# photodiode.net
KiCad netlist of a schematic drawn in EAGLE
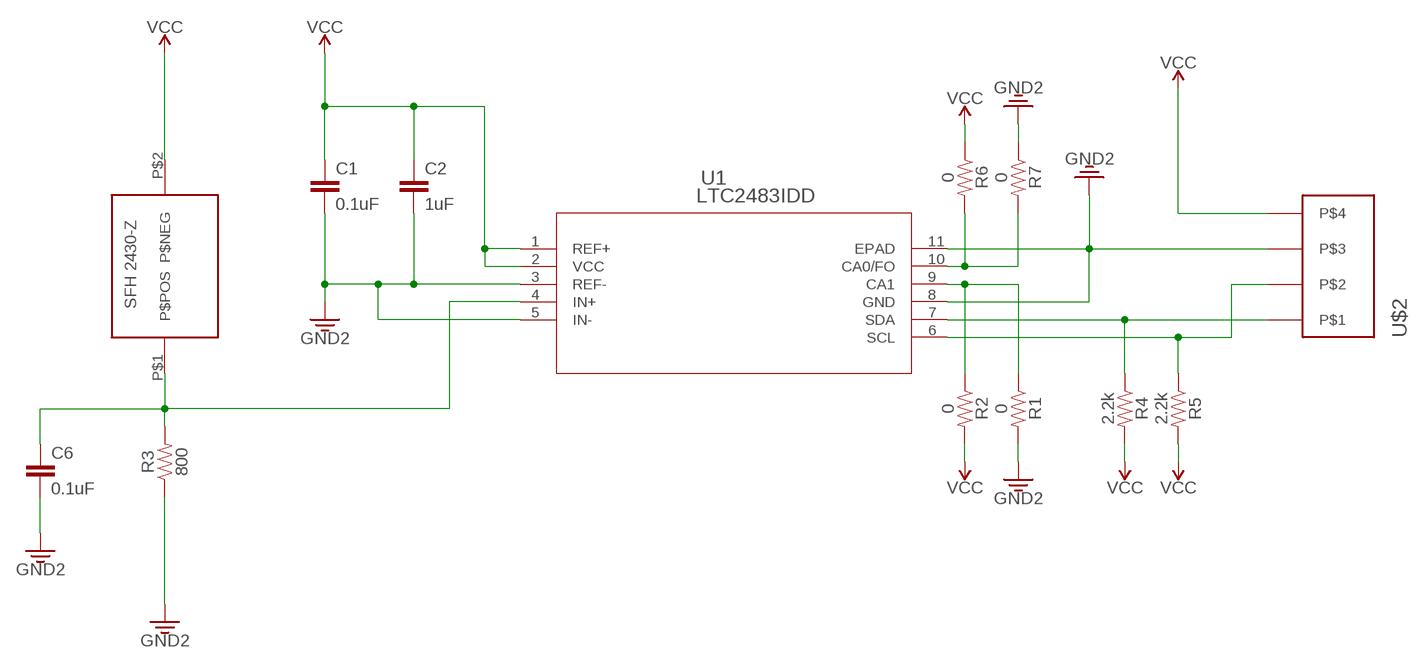
[diagram p0: schematic, sheet 1]

(export (version "E")
  (design (tool "Eeschema 10.0.6"))
  (components
    (comp (ref "C1")
      (value "0.1uF")
      (footprint "eagle-import:0603")
      (libsource (lib "eagle-import") (part "0.1UF-0603-100V-10%"))
    )
    (comp (ref "C2")
      (value "1uF")
      (footprint "eagle-import:0603")
      (libsource (lib "eagle-import") (part "0.1UF-0603-100V-10%"))
    )
    (comp (ref "C6")
      (value "0.1uF")
      (footprint "eagle-import:0603")
      (libsource (lib "eagle-import") (part "0.1UF-0603-100V-10%"))
    )
    (comp (ref "R1")
      (value "0")
      (footprint "eagle-import:0805")
      (libsource (lib "eagle-import") (part "RESISTOR0805"))
    )
    (comp (ref "R2")
      (value "0")
      (footprint "eagle-import:0805")
      (libsource (lib "eagle-import") (part "RESISTOR0805"))
    )
    (comp (ref "R3")
      (value "800")
      (footprint "eagle-import:0805")
      (libsource (lib "eagle-import") (part "RESISTOR0805"))
    )
    (comp (ref "R4")
      (value "2.2k")
      (footprint "eagle-import:0805")
      (libsource (lib "eagle-import") (part "RESISTOR0805"))
    )
    (comp (ref "R5")
      (value "2.2k")
      (footprint "eagle-import:0805")
      (libsource (lib "eagle-import") (part "RESISTOR0805"))
    )
    (comp (ref "R6")
      (value "0")
      (footprint "eagle-import:0805")
      (libsource (lib "eagle-import") (part "RESISTOR0805"))
    )
    (comp (ref "R7")
      (value "0")
      (footprint "eagle-import:0805")
      (libsource (lib "eagle-import") (part "RESISTOR0805"))
    )
    (comp (ref "U$1")
      (value "SFH-2430-Z")
      (footprint "eagle-import:DIL")
      (libsource (lib "eagle-import") (part "SFH-2430-Z"))
    )
    (comp (ref "U$2")
      (value "PICOLOCK_4PICOLOCK_4")
      (footprint "eagle-import:PICOLOCK_4")
      (libsource (lib "eagle-import") (part "PICOLOCK_4PICOLOCK_4"))
    )
    (comp (ref "U1")
      (value "LTC2483IDD")
      (footprint "eagle-import:DFN-10_DD")
      (fields (field (name "MANUFACTURER_PART_NUMBER") "ltc2483idd"))
      (libsource (lib "eagle-import") (part "LTC2483IDD"))
    )
  )
  (nets
    (net (code "1") (name "GND2") (class "Default")
      (node (ref "C1") (pin "2") (pinfunction "2_2") (pintype "passive"))
      (node (ref "C2") (pin "2") (pinfunction "2_2") (pintype "passive"))
      (node (ref "C6") (pin "2") (pinfunction "2_2") (pintype "passive"))
      (node (ref "R1") (pin "2") (pinfunction "2_2") (pintype "passive"))
      (node (ref "R3") (pin "1") (pinfunction "1_1") (pintype "passive"))
      (node (ref "R7") (pin "1") (pinfunction "1_1") (pintype "passive"))
      (node (ref "U$2") (pin "P$3") (pinfunction "P$3_P$3") (pintype "bidirectional"))
      (node (ref "U1") (pin "11") (pinfunction "EPAD_11") (pintype "passive"))
      (node (ref "U1") (pin "3") (pinfunction "REF-_3") (pintype "input"))
      (node (ref "U1") (pin "5") (pinfunction "IN-_5") (pintype "input"))
      (node (ref "U1") (pin "8") (pinfunction "GND_8") (pintype "power_in"))
    )
    (net (code "2") (name "Net-(U$1-P$POS)") (class "Default")
      (node (ref "C6") (pin "1") (pinfunction "1_1") (pintype "passive"))
      (node (ref "R3") (pin "2") (pinfunction "2_2") (pintype "passive"))
      (node (ref "U$1") (pin "P$1") (pinfunction "P$POS_P$1") (pintype "input"))
      (node (ref "U1") (pin "4") (pinfunction "IN+_4") (pintype "input"))
    )
    (net (code "3") (name "Net-(U1-CA0{slash}FO)") (class "Default")
      (node (ref "R6") (pin "2") (pinfunction "2_2") (pintype "passive"))
      (node (ref "R7") (pin "2") (pinfunction "2_2") (pintype "passive"))
      (node (ref "U1") (pin "10") (pinfunction "CA0/FO_10") (pintype "passive"))
    )
    (net (code "4") (name "Net-(U1-CA1)") (class "Default")
      (node (ref "R1") (pin "1") (pinfunction "1_1") (pintype "passive"))
      (node (ref "R2") (pin "1") (pinfunction "1_1") (pintype "passive"))
      (node (ref "U1") (pin "9") (pinfunction "CA1_9") (pintype "passive"))
    )
    (net (code "5") (name "Net-(U1-SCL)") (class "Default")
      (node (ref "R5") (pin "1") (pinfunction "1_1") (pintype "passive"))
      (node (ref "U$2") (pin "P$2") (pinfunction "P$2_P$2") (pintype "bidirectional"))
      (node (ref "U1") (pin "6") (pinfunction "SCL_6") (pintype "passive"))
    )
    (net (code "6") (name "Net-(U1-SDA)") (class "Default")
      (node (ref "R4") (pin "1") (pinfunction "1_1") (pintype "passive"))
      (node (ref "U$2") (pin "P$1") (pinfunction "P$1_P$1") (pintype "bidirectional"))
      (node (ref "U1") (pin "7") (pinfunction "SDA_7") (pintype "output"))
    )
    (net (code "7") (name "VCC") (class "Default")
      (node (ref "C1") (pin "1") (pinfunction "1_1") (pintype "passive"))
      (node (ref "C2") (pin "1") (pinfunction "1_1") (pintype "passive"))
      (node (ref "R2") (pin "2") (pinfunction "2_2") (pintype "passive"))
      (node (ref "R4") (pin "2") (pinfunction "2_2") (pintype "passive"))
      (node (ref "R5") (pin "2") (pinfunction "2_2") (pintype "passive"))
      (node (ref "R6") (pin "1") (pinfunction "1_1") (pintype "passive"))
      (node (ref "U$1") (pin "P$2") (pinfunction "P$NEG_P$2") (pintype "output"))
      (node (ref "U$2") (pin "P$4") (pinfunction "P$4_P$4") (pintype "bidirectional"))
      (node (ref "U1") (pin "1") (pinfunction "REF+_1") (pintype "input"))
      (node (ref "U1") (pin "2") (pinfunction "VCC_2") (pintype "power_in"))
    )
  )
)
